# steve_breakout.net
KiCad netlist of a schematic drawn in Altium Designer
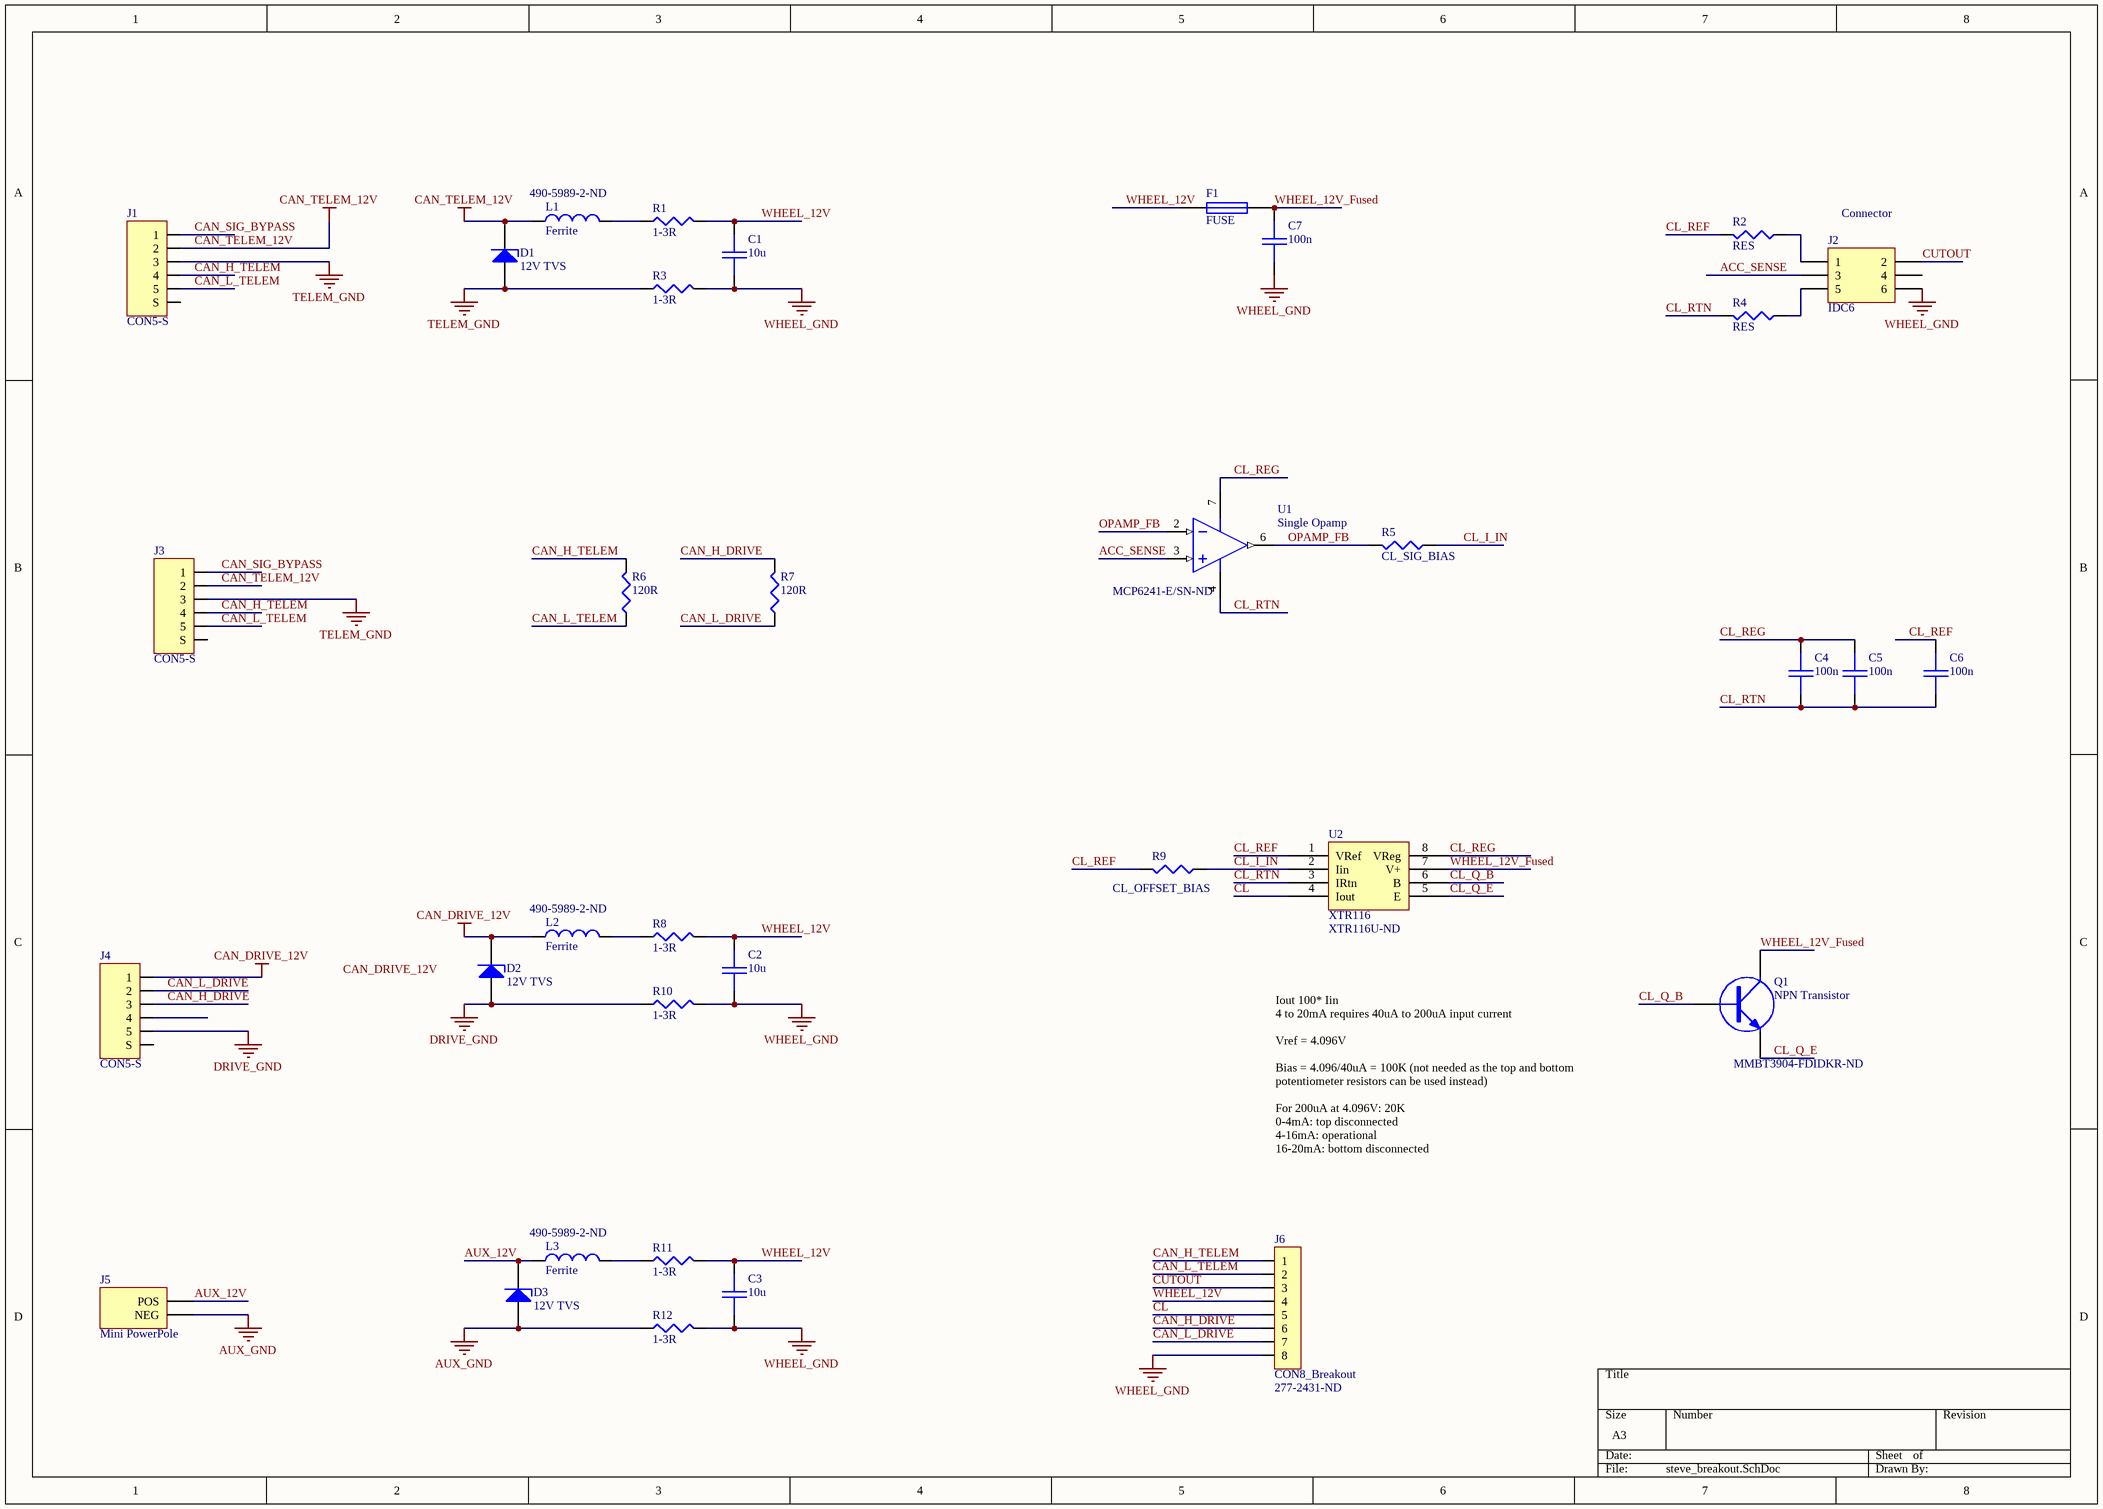
[diagram p0: steve_breakout.SchDoc]

(export (version "E")
  (design (tool "Eeschema 10.0.6"))
  (components
    (comp (ref "C1")
      (value "10u")
      (footprint "1206")
      (description "Capacitor")
      (libsource (lib "RCLDQ") (part "CAP"))
    )
    (comp (ref "C2")
      (value "10u")
      (footprint "1206")
      (description "Capacitor")
      (libsource (lib "RCLDQ") (part "CAP"))
    )
    (comp (ref "C3")
      (value "10u")
      (footprint "1206")
      (description "Capacitor")
      (libsource (lib "RCLDQ") (part "CAP"))
    )
    (comp (ref "C4")
      (value "100n")
      (footprint "0603")
      (description "Capacitor")
      (libsource (lib "RCLDQ") (part "CAP"))
    )
    (comp (ref "C5")
      (value "100n")
      (footprint "0603")
      (description "Capacitor")
      (libsource (lib "RCLDQ") (part "CAP"))
    )
    (comp (ref "C6")
      (value "100n")
      (footprint "0603")
      (description "Capacitor")
      (libsource (lib "RCLDQ") (part "CAP"))
    )
    (comp (ref "C7")
      (value "100n")
      (footprint "0603")
      (description "Capacitor")
      (libsource (lib "RCLDQ") (part "CAP"))
    )
    (comp (ref "D1")
      (value "12V TVS")
      (footprint "SMB")
      (description "Zener Diode")
      (libsource (lib "RCLDQ") (part "ZENER1"))
    )
    (comp (ref "D2")
      (value "12V TVS")
      (footprint "SMB")
      (description "Zener Diode")
      (libsource (lib "RCLDQ") (part "ZENER1"))
    )
    (comp (ref "D3")
      (value "12V TVS")
      (footprint "SMB")
      (description "Zener Diode")
      (libsource (lib "RCLDQ") (part "ZENER1"))
    )
    (comp (ref "F1")
      (value "FUSE")
      (footprint "LITTELFUSE-154")
      (description "Fuse")
      (libsource (lib "Miscellaneous") (part "FUSE"))
    )
    (comp (ref "J1")
      (value "CON5-S")
      (footprint "TRIAD5F")
      (description "Connector, 2 pin, with shield @ S")
      (libsource (lib "Connectors") (part "CON5-S"))
    )
    (comp (ref "J2")
      (value "IDC6")
      (footprint "IDC6")
      (description "Connector")
      (libsource (lib "Connectors") (part "IDC6"))
    )
    (comp (ref "J3")
      (value "CON5-S")
      (footprint "TRIAD5F")
      (description "Connector, 2 pin, with shield @ S")
      (libsource (lib "Connectors") (part "CON5-S"))
    )
    (comp (ref "J4")
      (value "CON5-S")
      (footprint "M12_5P")
      (description "Connector, 2 pin, with shield @ S")
      (libsource (lib "Connectors") (part "CON5-S"))
    )
    (comp (ref "J5")
      (value "Mini PowerPole")
      (footprint "POWERPOLE25A-2")
      (libsource (lib "steve_breakout") (part "PowerPole"))
    )
    (comp (ref "J6")
      (value "CON8_Breakout")
      (footprint "M12_8p")
      (description "277-2431-ND")
      (fields (field (name "SUPPLIER PART NUMBER 1") "277-2431-ND"))
      (libsource (lib "steve_breakout") (part "CON8_Breakout"))
    )
    (comp (ref "L1")
      (value "Ferrite")
      (footprint "1206")
      (description "Inductor")
      (fields
        (field (name "MANUFACTURER") "Generic Components")
        (field (name "SUPPLIER PART NUMBER 1") "490-5989-2-ND")
        (field (name "MANUFACTURER PART NUMBER") "BLM31PG330SN1L")
        (field (name "PUBLISHER") "Altium Limited")
      )
      (libsource (lib "RCLDQ") (part "INDUCTOR"))
    )
    (comp (ref "L2")
      (value "Ferrite")
      (footprint "1206")
      (description "Inductor")
      (fields
        (field (name "MANUFACTURER") "Generic Components")
        (field (name "SUPPLIER PART NUMBER 1") "490-5989-2-ND")
        (field (name "MANUFACTURER PART NUMBER") "BLM31PG330SN1L")
        (field (name "PUBLISHER") "Altium Limited")
      )
      (libsource (lib "RCLDQ") (part "INDUCTOR"))
    )
    (comp (ref "L3")
      (value "Ferrite")
      (footprint "1206")
      (description "Inductor")
      (fields
        (field (name "MANUFACTURER") "Generic Components")
        (field (name "SUPPLIER PART NUMBER 1") "490-5989-2-ND")
        (field (name "MANUFACTURER PART NUMBER") "BLM31PG330SN1L")
        (field (name "PUBLISHER") "Altium Limited")
      )
      (libsource (lib "RCLDQ") (part "INDUCTOR"))
    )
    (comp (ref "Q1")
      (value "NPN Transistor")
      (footprint "SOT23-3")
      (description "TRANS NPN 40V 350MW SMD SOT23-3")
      (fields
        (field (name "SUPPLIER PART NUMBER 1") "MMBT3904-FDIDKR-ND")
        (field (name "MANUFACTURER") "Diodes Inc")
        (field (name "MANUFACTURER PART NUMBER") "MMBT3904-7-F")
      )
      (libsource (lib "steve_breakout") (part "NPN Transistor"))
    )
    (comp (ref "R1")
      (value "1-3R")
      (footprint "1206")
      (description "Resistor")
      (libsource (lib "RCLDQ") (part "RES1"))
    )
    (comp (ref "R2")
      (value "RES")
      (footprint "0603")
      (description "Resistor")
      (libsource (lib "RCLDQ") (part "RES1"))
    )
    (comp (ref "R3")
      (value "1-3R")
      (footprint "1206")
      (description "Resistor")
      (libsource (lib "RCLDQ") (part "RES1"))
    )
    (comp (ref "R4")
      (value "RES")
      (footprint "0603")
      (description "Resistor")
      (libsource (lib "RCLDQ") (part "RES1"))
    )
    (comp (ref "R5")
      (value "CL_SIG_BIAS")
      (footprint "0603")
      (description "Resistor")
      (libsource (lib "RCLDQ") (part "RES1"))
    )
    (comp (ref "R6")
      (value "120R")
      (footprint "0603")
      (description "Resistor")
      (libsource (lib "RCLDQ") (part "RES1"))
    )
    (comp (ref "R7")
      (value "120R")
      (footprint "0603")
      (description "Resistor")
      (libsource (lib "RCLDQ") (part "RES1"))
    )
    (comp (ref "R8")
      (value "1-3R")
      (footprint "1206")
      (description "Resistor")
      (libsource (lib "RCLDQ") (part "RES1"))
    )
    (comp (ref "R9")
      (value "CL_OFFSET_BIAS")
      (footprint "0603")
      (description "Resistor")
      (libsource (lib "RCLDQ") (part "RES1"))
    )
    (comp (ref "R10")
      (value "1-3R")
      (footprint "1206")
      (description "Resistor")
      (libsource (lib "RCLDQ") (part "RES1"))
    )
    (comp (ref "R11")
      (value "1-3R")
      (footprint "1206")
      (description "Resistor")
      (libsource (lib "RCLDQ") (part "RES1"))
    )
    (comp (ref "R12")
      (value "1-3R")
      (footprint "1206")
      (description "Resistor")
      (libsource (lib "RCLDQ") (part "RES1"))
    )
    (comp (ref "U1")
      (value "Single Opamp")
      (footprint "SO8")
      (description "IC OPAMP SNGL 1.8V 550KHZ 8SOIC")
      (fields
        (field (name "SUPPLIER PART NUMBER 1") "MCP6241-E/SN-ND")
        (field (name "MANUFACTURER") "Microchip Technology")
        (field (name "MANUFACTURER PART NUMBER") "MCP6241-E/SN")
      )
      (libsource (lib "steve_breakout") (part "Single Opamp"))
    )
    (comp (ref "U2")
      (value "XTR116")
      (footprint "SO8")
      (description "4-20mA Current loop transmitter")
      (fields
        (field (name "MANUFACTURER") "Texas Instruments")
        (field (name "MANUFACTURER PART NUMBER") "XTR116U")
        (field (name "SUPPLIER PART NUMBER 1") "XTR116U-ND")
      )
      (libsource (lib "steve_breakout") (part "XTR116"))
    )
  )
  (nets
    (net (code "1") (name "/ACC_SENSE") (class "Default")
      (node (ref "J2") (pin "3") (pinfunction "3_3") (pintype "passive"))
      (node (ref "U1") (pin "3") (pinfunction "IN+_3") (pintype "input"))
    )
    (net (code "2") (name "/AUX_12V") (class "Default")
      (node (ref "D3") (pin "K") (pinfunction "K_K") (pintype "passive"))
      (node (ref "J5") (pin "POS") (pinfunction "POS_POS") (pintype "power_in"))
      (node (ref "L3") (pin "1") (pinfunction "1_1") (pintype "passive"))
    )
    (net (code "3") (name "/CAN_H_DRIVE") (class "Default")
      (node (ref "J4") (pin "3") (pinfunction "3_3") (pintype "bidirectional"))
      (node (ref "J6") (pin "6") (pinfunction "6_6") (pintype "passive"))
      (node (ref "R7") (pin "2") (pinfunction "2_2") (pintype "passive"))
    )
    (net (code "4") (name "/CAN_H_TELEM") (class "Default")
      (node (ref "J1") (pin "4") (pinfunction "4_4") (pintype "bidirectional"))
      (node (ref "J3") (pin "4") (pinfunction "4_4") (pintype "bidirectional"))
      (node (ref "J6") (pin "1") (pinfunction "1_1") (pintype "passive"))
      (node (ref "R6") (pin "2") (pinfunction "2_2") (pintype "passive"))
    )
    (net (code "5") (name "/CAN_L_DRIVE") (class "Default")
      (node (ref "J4") (pin "2") (pinfunction "2_2") (pintype "bidirectional"))
      (node (ref "J6") (pin "7") (pinfunction "7_7") (pintype "passive"))
      (node (ref "R7") (pin "1") (pinfunction "1_1") (pintype "passive"))
    )
    (net (code "6") (name "/CAN_L_TELEM") (class "Default")
      (node (ref "J1") (pin "5") (pinfunction "5_5") (pintype "bidirectional"))
      (node (ref "J3") (pin "5") (pinfunction "5_5") (pintype "bidirectional"))
      (node (ref "J6") (pin "2") (pinfunction "2_2") (pintype "passive"))
      (node (ref "R6") (pin "1") (pinfunction "1_1") (pintype "passive"))
    )
    (net (code "7") (name "/CAN_SIG_BYPASS") (class "Default")
      (node (ref "J1") (pin "1") (pinfunction "1_1") (pintype "bidirectional"))
      (node (ref "J3") (pin "1") (pinfunction "1_1") (pintype "bidirectional"))
    )
    (net (code "8") (name "/CL") (class "Default")
      (node (ref "J6") (pin "5") (pinfunction "5_5") (pintype "passive"))
      (node (ref "U2") (pin "4") (pinfunction "Iout_4") (pintype "passive"))
    )
    (net (code "9") (name "/CL_I_IN") (class "Default")
      (node (ref "R5") (pin "1") (pinfunction "1_1") (pintype "passive"))
      (node (ref "R9") (pin "1") (pinfunction "1_1") (pintype "passive"))
      (node (ref "U2") (pin "2") (pinfunction "Iin_2") (pintype "passive"))
    )
    (net (code "10") (name "/CL_Q_B") (class "Default")
      (node (ref "Q1") (pin "1") (pinfunction "B_1") (pintype "passive"))
      (node (ref "U2") (pin "6") (pinfunction "B_6") (pintype "passive"))
    )
    (net (code "11") (name "/CL_Q_E") (class "Default")
      (node (ref "Q1") (pin "2") (pinfunction "E_2") (pintype "passive"))
      (node (ref "U2") (pin "5") (pinfunction "E_5") (pintype "passive"))
    )
    (net (code "12") (name "/CL_REF") (class "Default")
      (node (ref "C6") (pin "1") (pinfunction "1_1") (pintype "passive"))
      (node (ref "R2") (pin "2") (pinfunction "2_2") (pintype "passive"))
      (node (ref "R9") (pin "2") (pinfunction "2_2") (pintype "passive"))
      (node (ref "U2") (pin "1") (pinfunction "VRef_1") (pintype "passive"))
    )
    (net (code "13") (name "/CL_REG") (class "Default")
      (node (ref "C4") (pin "1") (pinfunction "1_1") (pintype "passive"))
      (node (ref "C5") (pin "1") (pinfunction "1_1") (pintype "passive"))
      (node (ref "U1") (pin "7") (pinfunction "V+_7") (pintype "power_in"))
      (node (ref "U2") (pin "8") (pinfunction "VReg_8") (pintype "passive"))
    )
    (net (code "14") (name "/CL_RTN") (class "Default")
      (node (ref "C4") (pin "2") (pinfunction "2_2") (pintype "passive"))
      (node (ref "C5") (pin "2") (pinfunction "2_2") (pintype "passive"))
      (node (ref "C6") (pin "2") (pinfunction "2_2") (pintype "passive"))
      (node (ref "R4") (pin "2") (pinfunction "2_2") (pintype "passive"))
      (node (ref "U1") (pin "4") (pinfunction "V+_4") (pintype "power_in"))
      (node (ref "U2") (pin "3") (pinfunction "IRtn_3") (pintype "passive"))
    )
    (net (code "15") (name "/CUTOUT") (class "Default")
      (node (ref "J2") (pin "2") (pinfunction "2_2") (pintype "passive"))
      (node (ref "J6") (pin "3") (pinfunction "3_3") (pintype "passive"))
    )
    (net (code "16") (name "/OPAMP_FB") (class "Default")
      (node (ref "R5") (pin "2") (pinfunction "2_2") (pintype "passive"))
      (node (ref "U1") (pin "2") (pinfunction "IN-_2") (pintype "input"))
      (node (ref "U1") (pin "6") (pinfunction "OUT_6") (pintype "output"))
    )
    (net (code "17") (name "/WHEEL_12V") (class "Default")
      (node (ref "C1") (pin "1") (pinfunction "1_1") (pintype "passive"))
      (node (ref "C2") (pin "1") (pinfunction "1_1") (pintype "passive"))
      (node (ref "C3") (pin "1") (pinfunction "1_1") (pintype "passive"))
      (node (ref "F1") (pin "1") (pinfunction "1_1") (pintype "passive"))
      (node (ref "J6") (pin "4") (pinfunction "4_4") (pintype "passive"))
      (node (ref "R1") (pin "2") (pinfunction "2_2") (pintype "passive"))
      (node (ref "R11") (pin "2") (pinfunction "2_2") (pintype "passive"))
      (node (ref "R8") (pin "2") (pinfunction "2_2") (pintype "passive"))
    )
    (net (code "18") (name "/WHEEL_12V_Fused") (class "Default")
      (node (ref "C7") (pin "1") (pinfunction "1_1") (pintype "passive"))
      (node (ref "F1") (pin "2") (pinfunction "2_2") (pintype "passive"))
      (node (ref "Q1") (pin "3") (pinfunction "C_3") (pintype "passive"))
      (node (ref "U2") (pin "7") (pinfunction "V+_7") (pintype "passive"))
    )
    (net (code "19") (name "AUX_GND") (class "Default")
      (node (ref "D3") (pin "A") (pinfunction "A_A") (pintype "passive"))
      (node (ref "J5") (pin "NEG") (pinfunction "NEG_NEG") (pintype "power_in"))
      (node (ref "R12") (pin "1") (pinfunction "1_1") (pintype "passive"))
    )
    (net (code "20") (name "CAN_DRIVE_12V") (class "Default")
      (node (ref "D2") (pin "K") (pinfunction "K_K") (pintype "passive"))
      (node (ref "J4") (pin "1") (pinfunction "1_1") (pintype "bidirectional"))
      (node (ref "L2") (pin "1") (pinfunction "1_1") (pintype "passive"))
    )
    (net (code "21") (name "CAN_TELEM_12V") (class "Default")
      (node (ref "D1") (pin "K") (pinfunction "K_K") (pintype "passive"))
      (node (ref "J1") (pin "2") (pinfunction "2_2") (pintype "bidirectional"))
      (node (ref "J3") (pin "2") (pinfunction "2_2") (pintype "bidirectional"))
      (node (ref "L1") (pin "1") (pinfunction "1_1") (pintype "passive"))
    )
    (net (code "22") (name "DRIVE_GND") (class "Default")
      (node (ref "D2") (pin "A") (pinfunction "A_A") (pintype "passive"))
      (node (ref "J4") (pin "5") (pinfunction "5_5") (pintype "bidirectional"))
      (node (ref "R10") (pin "1") (pinfunction "1_1") (pintype "passive"))
    )
    (net (code "23") (name "Net-(J2-Pad1)") (class "Default")
      (node (ref "J2") (pin "1") (pinfunction "1_1") (pintype "passive"))
      (node (ref "R2") (pin "1") (pinfunction "1_1") (pintype "passive"))
    )
    (net (code "24") (name "Net-(J2-Pad5)") (class "Default")
      (node (ref "J2") (pin "5") (pinfunction "5_5") (pintype "passive"))
      (node (ref "R4") (pin "1") (pinfunction "1_1") (pintype "passive"))
    )
    (net (code "25") (name "Net-(L1-Pad2)") (class "Default")
      (node (ref "L1") (pin "2") (pinfunction "2_2") (pintype "passive"))
      (node (ref "R1") (pin "1") (pinfunction "1_1") (pintype "passive"))
    )
    (net (code "26") (name "Net-(L2-Pad2)") (class "Default")
      (node (ref "L2") (pin "2") (pinfunction "2_2") (pintype "passive"))
      (node (ref "R8") (pin "1") (pinfunction "1_1") (pintype "passive"))
    )
    (net (code "27") (name "Net-(L3-Pad2)") (class "Default")
      (node (ref "L3") (pin "2") (pinfunction "2_2") (pintype "passive"))
      (node (ref "R11") (pin "1") (pinfunction "1_1") (pintype "passive"))
    )
    (net (code "28") (name "TELEM_GND") (class "Default")
      (node (ref "D1") (pin "A") (pinfunction "A_A") (pintype "passive"))
      (node (ref "J1") (pin "3") (pinfunction "3_3") (pintype "bidirectional"))
      (node (ref "J3") (pin "3") (pinfunction "3_3") (pintype "bidirectional"))
      (node (ref "R3") (pin "1") (pinfunction "1_1") (pintype "passive"))
    )
    (net (code "29") (name "WHEEL_GND") (class "Default")
      (node (ref "C1") (pin "2") (pinfunction "2_2") (pintype "passive"))
      (node (ref "C2") (pin "2") (pinfunction "2_2") (pintype "passive"))
      (node (ref "C3") (pin "2") (pinfunction "2_2") (pintype "passive"))
      (node (ref "C7") (pin "2") (pinfunction "2_2") (pintype "passive"))
      (node (ref "J2") (pin "6") (pinfunction "6_6") (pintype "passive"))
      (node (ref "J6") (pin "8") (pinfunction "8_8") (pintype "passive"))
      (node (ref "R10") (pin "2") (pinfunction "2_2") (pintype "passive"))
      (node (ref "R12") (pin "2") (pinfunction "2_2") (pintype "passive"))
      (node (ref "R3") (pin "2") (pinfunction "2_2") (pintype "passive"))
    )
    (net (code "30") (name "unconnected-(J1-S-Pad0)") (class "Default")
      (node (ref "J1") (pin "0") (pinfunction "S_0") (pintype "power_in"))
    )
    (net (code "31") (name "unconnected-(J2-Pad4)") (class "Default")
      (node (ref "J2") (pin "4") (pinfunction "4_4") (pintype "passive"))
    )
    (net (code "32") (name "unconnected-(J3-S-Pad0)") (class "Default")
      (node (ref "J3") (pin "0") (pinfunction "S_0") (pintype "power_in"))
    )
    (net (code "33") (name "unconnected-(J4-Pad4)") (class "Default")
      (node (ref "J4") (pin "4") (pinfunction "4_4") (pintype "bidirectional"))
    )
    (net (code "34") (name "unconnected-(J4-S-Pad0)") (class "Default")
      (node (ref "J4") (pin "0") (pinfunction "S_0") (pintype "power_in"))
    )
  )
)
